# 4-USB-A.net
KiCad netlist of a schematic drawn in Altium Designer
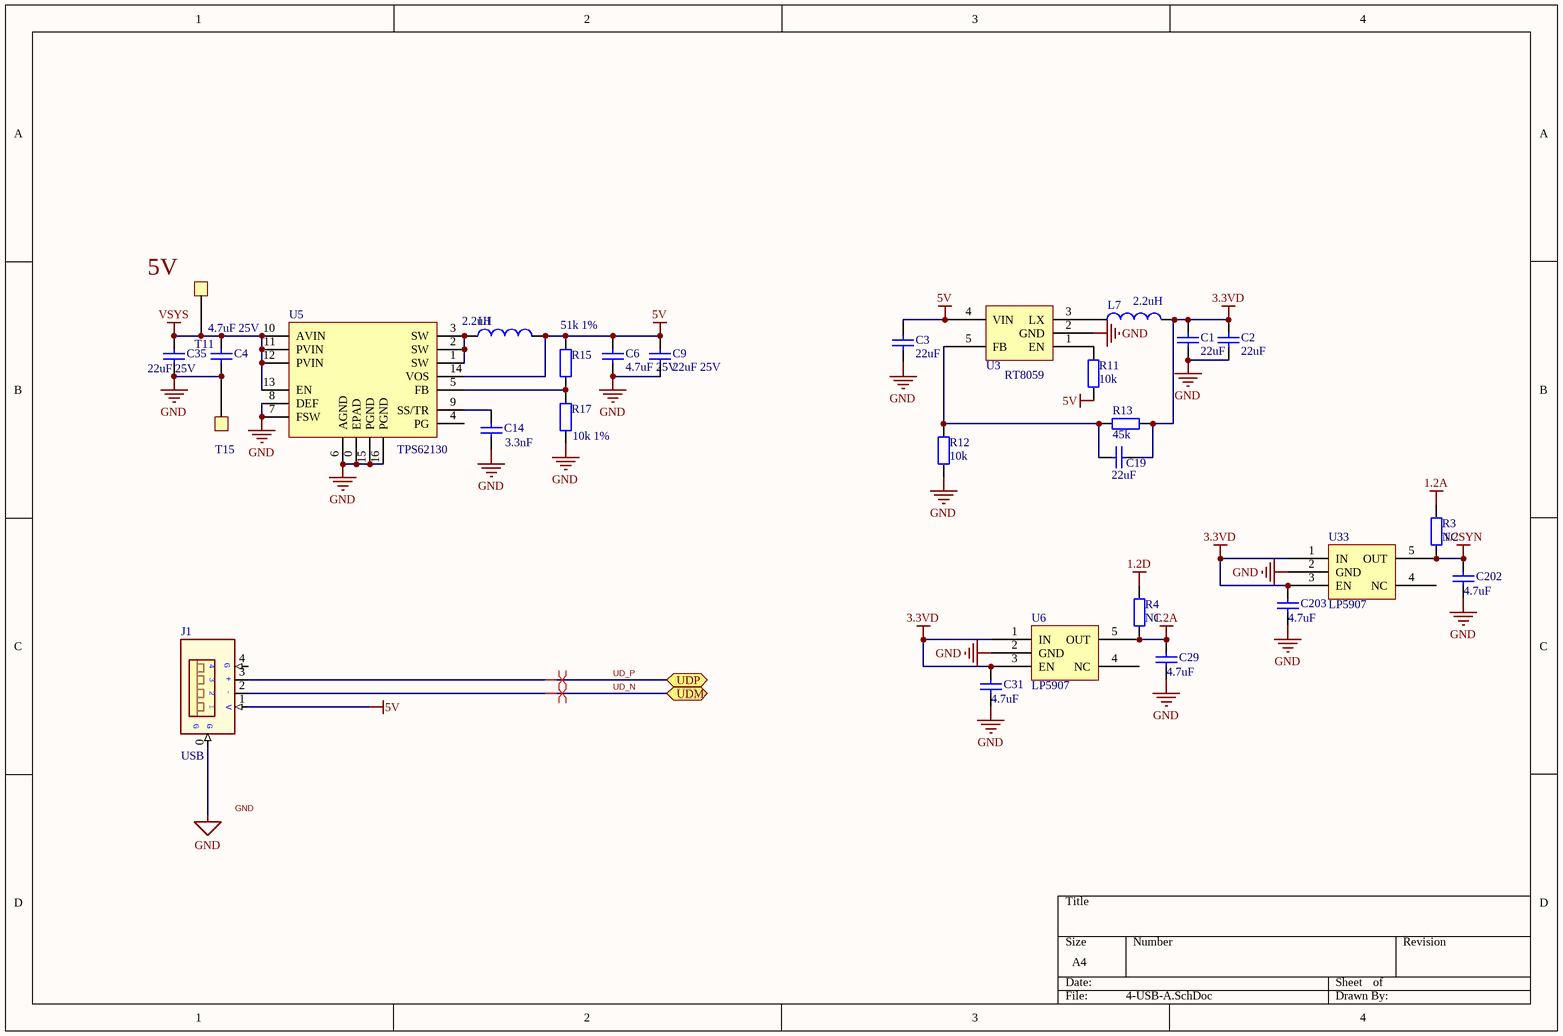
[diagram p0: 4-USB-A.SchDoc]

(export (version "E")
  (design (tool "Eeschema 10.0.6"))
  (components
    (comp (ref "C1")
      (value "22uF")
      (footprint "0805")
      (description "Capacitor")
      (fields (field (name "Comment") "Cap") (field (name "PUBLISHER") "Altium Limited"))
      (libsource (lib "RTC6705") (part "Cap"))
    )
    (comp (ref "C2")
      (value "22uF")
      (footprint "0805")
      (description "Capacitor")
      (fields (field (name "Comment") "Cap") (field (name "PUBLISHER") "Altium Limited"))
      (libsource (lib "RTC6705") (part "Cap"))
    )
    (comp (ref "C3")
      (value "22uF")
      (footprint "0805")
      (description "Capacitor")
      (fields (field (name "Comment") "Cap") (field (name "PUBLISHER") "Altium Limited"))
      (libsource (lib "RTC6705") (part "Cap"))
    )
    (comp (ref "C4")
      (value "4.7uF 25V")
      (footprint "0805")
      (description "Capacitor")
      (fields (field (name "Comment") "Cap") (field (name "PUBLISHER") "Altium Limited"))
      (libsource (lib "RTC6705") (part "Cap"))
    )
    (comp (ref "C6")
      (value "4.7uF 25V")
      (footprint "0805")
      (description "Capacitor")
      (fields (field (name "Comment") "Cap") (field (name "PUBLISHER") "Altium Limited"))
      (libsource (lib "RTC6705") (part "Cap"))
    )
    (comp (ref "C9")
      (value "22uF 25V")
      (footprint "1210")
      (description "Capacitor")
      (fields (field (name "Comment") "Cap") (field (name "PUBLISHER") "Altium Limited"))
      (libsource (lib "RTC6705") (part "Cap"))
    )
    (comp (ref "C14")
      (value "3.3nF")
      (footprint "0402")
      (description "Capacitor")
      (fields (field (name "PUBLISHER") "Altium Limited"))
      (libsource (lib "RTC6705") (part "Cap"))
    )
    (comp (ref "C19")
      (value "22uF")
      (footprint "0402")
      (description "Capacitor")
      (fields (field (name "Comment") "Cap") (field (name "PUBLISHER") "Altium Limited"))
      (libsource (lib "RTC6705") (part "Cap"))
    )
    (comp (ref "C29")
      (value "4.7uF")
      (footprint "0603")
      (description "Capacitor")
      (fields (field (name "PUBLISHER") "Altium Limited"))
      (libsource (lib "RTC6705") (part "Cap"))
    )
    (comp (ref "C31")
      (value "4.7uF")
      (footprint "0603")
      (description "Capacitor")
      (fields (field (name "PUBLISHER") "Altium Limited"))
      (libsource (lib "RTC6705") (part "Cap"))
    )
    (comp (ref "C35")
      (value "22uF 25V")
      (footprint "1210")
      (description "Capacitor")
      (fields (field (name "Comment") "Cap") (field (name "PUBLISHER") "Altium Limited"))
      (libsource (lib "RTC6705") (part "Cap"))
    )
    (comp (ref "C202")
      (value "4.7uF")
      (footprint "0603")
      (description "Capacitor")
      (fields (field (name "PUBLISHER") "Altium Limited"))
      (libsource (lib "RTC6705") (part "Cap"))
    )
    (comp (ref "C203")
      (value "4.7uF")
      (footprint "0603")
      (description "Capacitor")
      (fields (field (name "PUBLISHER") "Altium Limited"))
      (libsource (lib "RTC6705") (part "Cap"))
    )
    (comp (ref "J1") (value "USB") (footprint "USB-A-MALE") (libsource (lib "Euler") (part "USB")))
    (comp (ref "L1")
      (value "2.2uH")
      (footprint "L4015")
      (description "Inductor")
      (fields (field (name "PUBLISHER") "Altium Limited"))
      (libsource (lib "Miscellaneous Devices") (part "Inductor"))
    )
    (comp (ref "L7")
      (value "2.2uH")
      (footprint "0806")
      (description "Inductor")
      (fields (field (name "PUBLISHER") "Altium Limited"))
      (libsource (lib "Miscellaneous Devices") (part "Inductor"))
    )
    (comp (ref "R3")
      (value "NC")
      (footprint "0402")
      (description "Resistor")
      (fields (field (name "PUBLISHER") "Altium Limited"))
      (libsource (lib "") (part "Res2_1"))
    )
    (comp (ref "R4")
      (value "NC")
      (footprint "0402")
      (description "Resistor")
      (fields (field (name "PUBLISHER") "Altium Limited"))
      (libsource (lib "") (part "Res2_1"))
    )
    (comp (ref "R11")
      (value "10k")
      (footprint "0402")
      (description "Resistor")
      (fields (field (name "PUBLISHER") "Altium Limited"))
      (libsource (lib "") (part "Res2_2"))
    )
    (comp (ref "R12")
      (value "10k")
      (footprint "0402")
      (description "Resistor")
      (fields (field (name "PUBLISHER") "Altium Limited"))
      (libsource (lib "") (part "Res2_1"))
    )
    (comp (ref "R13")
      (value "45k")
      (footprint "0402")
      (description "Resistor")
      (fields (field (name "PUBLISHER") "Altium Limited"))
      (libsource (lib "RTC6705") (part "Res2"))
    )
    (comp (ref "R15")
      (value "51k 1%")
      (footprint "0402")
      (description "Resistor")
      (fields (field (name "PUBLISHER") "Altium Limited"))
      (libsource (lib "") (part "Res2_2"))
    )
    (comp (ref "R17")
      (value "10k 1%")
      (footprint "0402")
      (description "Resistor")
      (fields (field (name "PUBLISHER") "Altium Limited"))
      (libsource (lib "") (part "Res2_2"))
    )
    (comp (ref "T11") (value "TestPad") (footprint "TestPad") (libsource (lib "sch") (part "TestPad")))
    (comp (ref "T15") (value "TestPad") (footprint "TestPad") (libsource (lib "") (part "TestPad_1")))
    (comp (ref "U3") (value "RT8059") (footprint "SOT23-5") (libsource (lib "WifiGain") (part "RT8059")))
    (comp (ref "U5") (value "TPS62130") (footprint "TPS62130") (libsource (lib "sch") (part "TPS62130")))
    (comp (ref "U6") (value "LP5907") (footprint "SOT23-5") (libsource (lib "RTC6705") (part "LP5907")))
    (comp (ref "U33") (value "LP5907") (footprint "SOT23-5") (libsource (lib "RTC6705") (part "LP5907")))
  )
  (nets
    (net (code "1") (name "/UD_N") (class "Default")
      (node (ref "J1") (pin "2") (pinfunction "D-_2") (pintype "tri_state"))
    )
    (net (code "2") (name "/UD_P") (class "Default")
      (node (ref "J1") (pin "3") (pinfunction "D+_3") (pintype "tri_state"))
    )
    (net (code "3") (name "1.2A") (class "Default")
      (node (ref "C29") (pin "2") (pinfunction "2_2") (pintype "passive"))
      (node (ref "R3") (pin "2") (pinfunction "2_2") (pintype "passive"))
      (node (ref "R4") (pin "1") (pinfunction "1_1") (pintype "passive"))
      (node (ref "U6") (pin "5") (pinfunction "OUT_5") (pintype "passive"))
    )
    (net (code "4") (name "1.2D") (class "Default")
      (node (ref "R4") (pin "2") (pinfunction "2_2") (pintype "passive"))
    )
    (net (code "5") (name "1.2SYN") (class "Default")
      (node (ref "C202") (pin "2") (pinfunction "2_2") (pintype "passive"))
      (node (ref "R3") (pin "1") (pinfunction "1_1") (pintype "passive"))
      (node (ref "U33") (pin "5") (pinfunction "OUT_5") (pintype "passive"))
    )
    (net (code "6") (name "3.3VD") (class "Default")
      (node (ref "C1") (pin "2") (pinfunction "2_2") (pintype "passive"))
      (node (ref "C19") (pin "1") (pinfunction "1_1") (pintype "passive"))
      (node (ref "C2") (pin "2") (pinfunction "2_2") (pintype "passive"))
      (node (ref "C203") (pin "2") (pinfunction "2_2") (pintype "passive"))
      (node (ref "C31") (pin "2") (pinfunction "2_2") (pintype "passive"))
      (node (ref "L7") (pin "2") (pinfunction "2_2") (pintype "passive"))
      (node (ref "R13") (pin "2") (pinfunction "2_2") (pintype "passive"))
      (node (ref "U33") (pin "1") (pinfunction "IN_1") (pintype "passive"))
      (node (ref "U33") (pin "3") (pinfunction "EN_3") (pintype "passive"))
      (node (ref "U6") (pin "1") (pinfunction "IN_1") (pintype "passive"))
      (node (ref "U6") (pin "3") (pinfunction "EN_3") (pintype "passive"))
    )
    (net (code "7") (name "5V") (class "Default")
      (node (ref "C3") (pin "2") (pinfunction "2_2") (pintype "passive"))
      (node (ref "C6") (pin "2") (pinfunction "2_2") (pintype "passive"))
      (node (ref "C9") (pin "2") (pinfunction "2_2") (pintype "passive"))
      (node (ref "J1") (pin "1") (pinfunction "V+_1") (pintype "input"))
      (node (ref "L1") (pin "2") (pinfunction "2_2") (pintype "passive"))
      (node (ref "R11") (pin "2") (pinfunction "2_2") (pintype "passive"))
      (node (ref "R15") (pin "1") (pinfunction "1_1") (pintype "passive"))
      (node (ref "U3") (pin "4") (pinfunction "VIN_4") (pintype "passive"))
      (node (ref "U5") (pin "14") (pinfunction "VOS_14") (pintype "passive"))
    )
    (net (code "8") (name "GND") (class "Default")
      (node (ref "C1") (pin "1") (pinfunction "1_1") (pintype "passive"))
      (node (ref "C14") (pin "2") (pinfunction "2_2") (pintype "passive"))
      (node (ref "C2") (pin "1") (pinfunction "1_1") (pintype "passive"))
      (node (ref "C202") (pin "1") (pinfunction "1_1") (pintype "passive"))
      (node (ref "C203") (pin "1") (pinfunction "1_1") (pintype "passive"))
      (node (ref "C29") (pin "1") (pinfunction "1_1") (pintype "passive"))
      (node (ref "C3") (pin "1") (pinfunction "1_1") (pintype "passive"))
      (node (ref "C31") (pin "1") (pinfunction "1_1") (pintype "passive"))
      (node (ref "C35") (pin "2") (pinfunction "2_2") (pintype "passive"))
      (node (ref "C4") (pin "2") (pinfunction "2_2") (pintype "passive"))
      (node (ref "C6") (pin "1") (pinfunction "1_1") (pintype "passive"))
      (node (ref "C9") (pin "1") (pinfunction "1_1") (pintype "passive"))
      (node (ref "J1") (pin "0") (pinfunction "G_0") (pintype "input"))
      (node (ref "R12") (pin "1") (pinfunction "1_1") (pintype "passive"))
      (node (ref "R17") (pin "2") (pinfunction "2_2") (pintype "passive"))
      (node (ref "T15") (pin "1") (pinfunction "3_1") (pintype "passive"))
      (node (ref "U3") (pin "2") (pinfunction "GND_2") (pintype "passive"))
      (node (ref "U33") (pin "2") (pinfunction "GND_2") (pintype "passive"))
      (node (ref "U5") (pin "0") (pinfunction "EPAD_0") (pintype "passive"))
      (node (ref "U5") (pin "15") (pinfunction "PGND_15") (pintype "passive"))
      (node (ref "U5") (pin "16") (pinfunction "PGND_16") (pintype "passive"))
      (node (ref "U5") (pin "6") (pinfunction "AGND_6") (pintype "passive"))
      (node (ref "U5") (pin "7") (pinfunction "FSW_7") (pintype "passive"))
      (node (ref "U5") (pin "8") (pinfunction "DEF_8") (pintype "passive"))
      (node (ref "U6") (pin "2") (pinfunction "GND_2") (pintype "passive"))
    )
    (net (code "9") (name "Net-(L1-Pad1)") (class "Default")
      (node (ref "L1") (pin "1") (pinfunction "1_1") (pintype "passive"))
      (node (ref "U5") (pin "1") (pinfunction "SW_1") (pintype "passive"))
      (node (ref "U5") (pin "2") (pinfunction "SW_2") (pintype "passive"))
      (node (ref "U5") (pin "3") (pinfunction "SW_3") (pintype "passive"))
    )
    (net (code "10") (name "Net-(U3-EN)") (class "Default")
      (node (ref "R11") (pin "1") (pinfunction "1_1") (pintype "passive"))
      (node (ref "U3") (pin "1") (pinfunction "EN_1") (pintype "passive"))
    )
    (net (code "11") (name "Net-(U3-FB)") (class "Default")
      (node (ref "C19") (pin "2") (pinfunction "2_2") (pintype "passive"))
      (node (ref "R12") (pin "2") (pinfunction "2_2") (pintype "passive"))
      (node (ref "R13") (pin "1") (pinfunction "1_1") (pintype "passive"))
      (node (ref "U3") (pin "5") (pinfunction "FB_5") (pintype "passive"))
    )
    (net (code "12") (name "Net-(U3-LX)") (class "Default")
      (node (ref "L7") (pin "1") (pinfunction "1_1") (pintype "passive"))
      (node (ref "U3") (pin "3") (pinfunction "LX_3") (pintype "passive"))
    )
    (net (code "13") (name "Net-(U5-FB)") (class "Default")
      (node (ref "R15") (pin "2") (pinfunction "2_2") (pintype "passive"))
      (node (ref "R17") (pin "1") (pinfunction "1_1") (pintype "passive"))
      (node (ref "U5") (pin "5") (pinfunction "FB_5") (pintype "passive"))
    )
    (net (code "14") (name "Net-(U5-SS{slash}TR)") (class "Default")
      (node (ref "C14") (pin "1") (pinfunction "1_1") (pintype "passive"))
      (node (ref "U5") (pin "9") (pinfunction "SS/TR_9") (pintype "passive"))
    )
    (net (code "15") (name "VSYS") (class "Default")
      (node (ref "C35") (pin "1") (pinfunction "1_1") (pintype "passive"))
      (node (ref "C4") (pin "1") (pinfunction "1_1") (pintype "passive"))
      (node (ref "T11") (pin "1") (pinfunction "3_1") (pintype "passive"))
      (node (ref "U5") (pin "10") (pinfunction "AVIN_10") (pintype "passive"))
      (node (ref "U5") (pin "11") (pinfunction "PVIN_11") (pintype "passive"))
      (node (ref "U5") (pin "12") (pinfunction "PVIN_12") (pintype "passive"))
      (node (ref "U5") (pin "13") (pinfunction "EN_13") (pintype "passive"))
    )
    (net (code "16") (name "unconnected-(J1-G-Pad4)") (class "Default")
      (node (ref "J1") (pin "4") (pinfunction "G_4") (pintype "input"))
    )
    (net (code "17") (name "unconnected-(U5-PG-Pad4)") (class "Default")
      (node (ref "U5") (pin "4") (pinfunction "PG_4") (pintype "passive"))
    )
    (net (code "18") (name "unconnected-(U6-NC-Pad4)") (class "Default")
      (node (ref "U6") (pin "4") (pinfunction "NC_4") (pintype "passive"))
    )
    (net (code "19") (name "unconnected-(U33-NC-Pad4)") (class "Default")
      (node (ref "U33") (pin "4") (pinfunction "NC_4") (pintype "passive"))
    )
  )
)
